# Steering_Converter_DRV8833C.net
KiCad netlist of a schematic drawn in Altium Designer
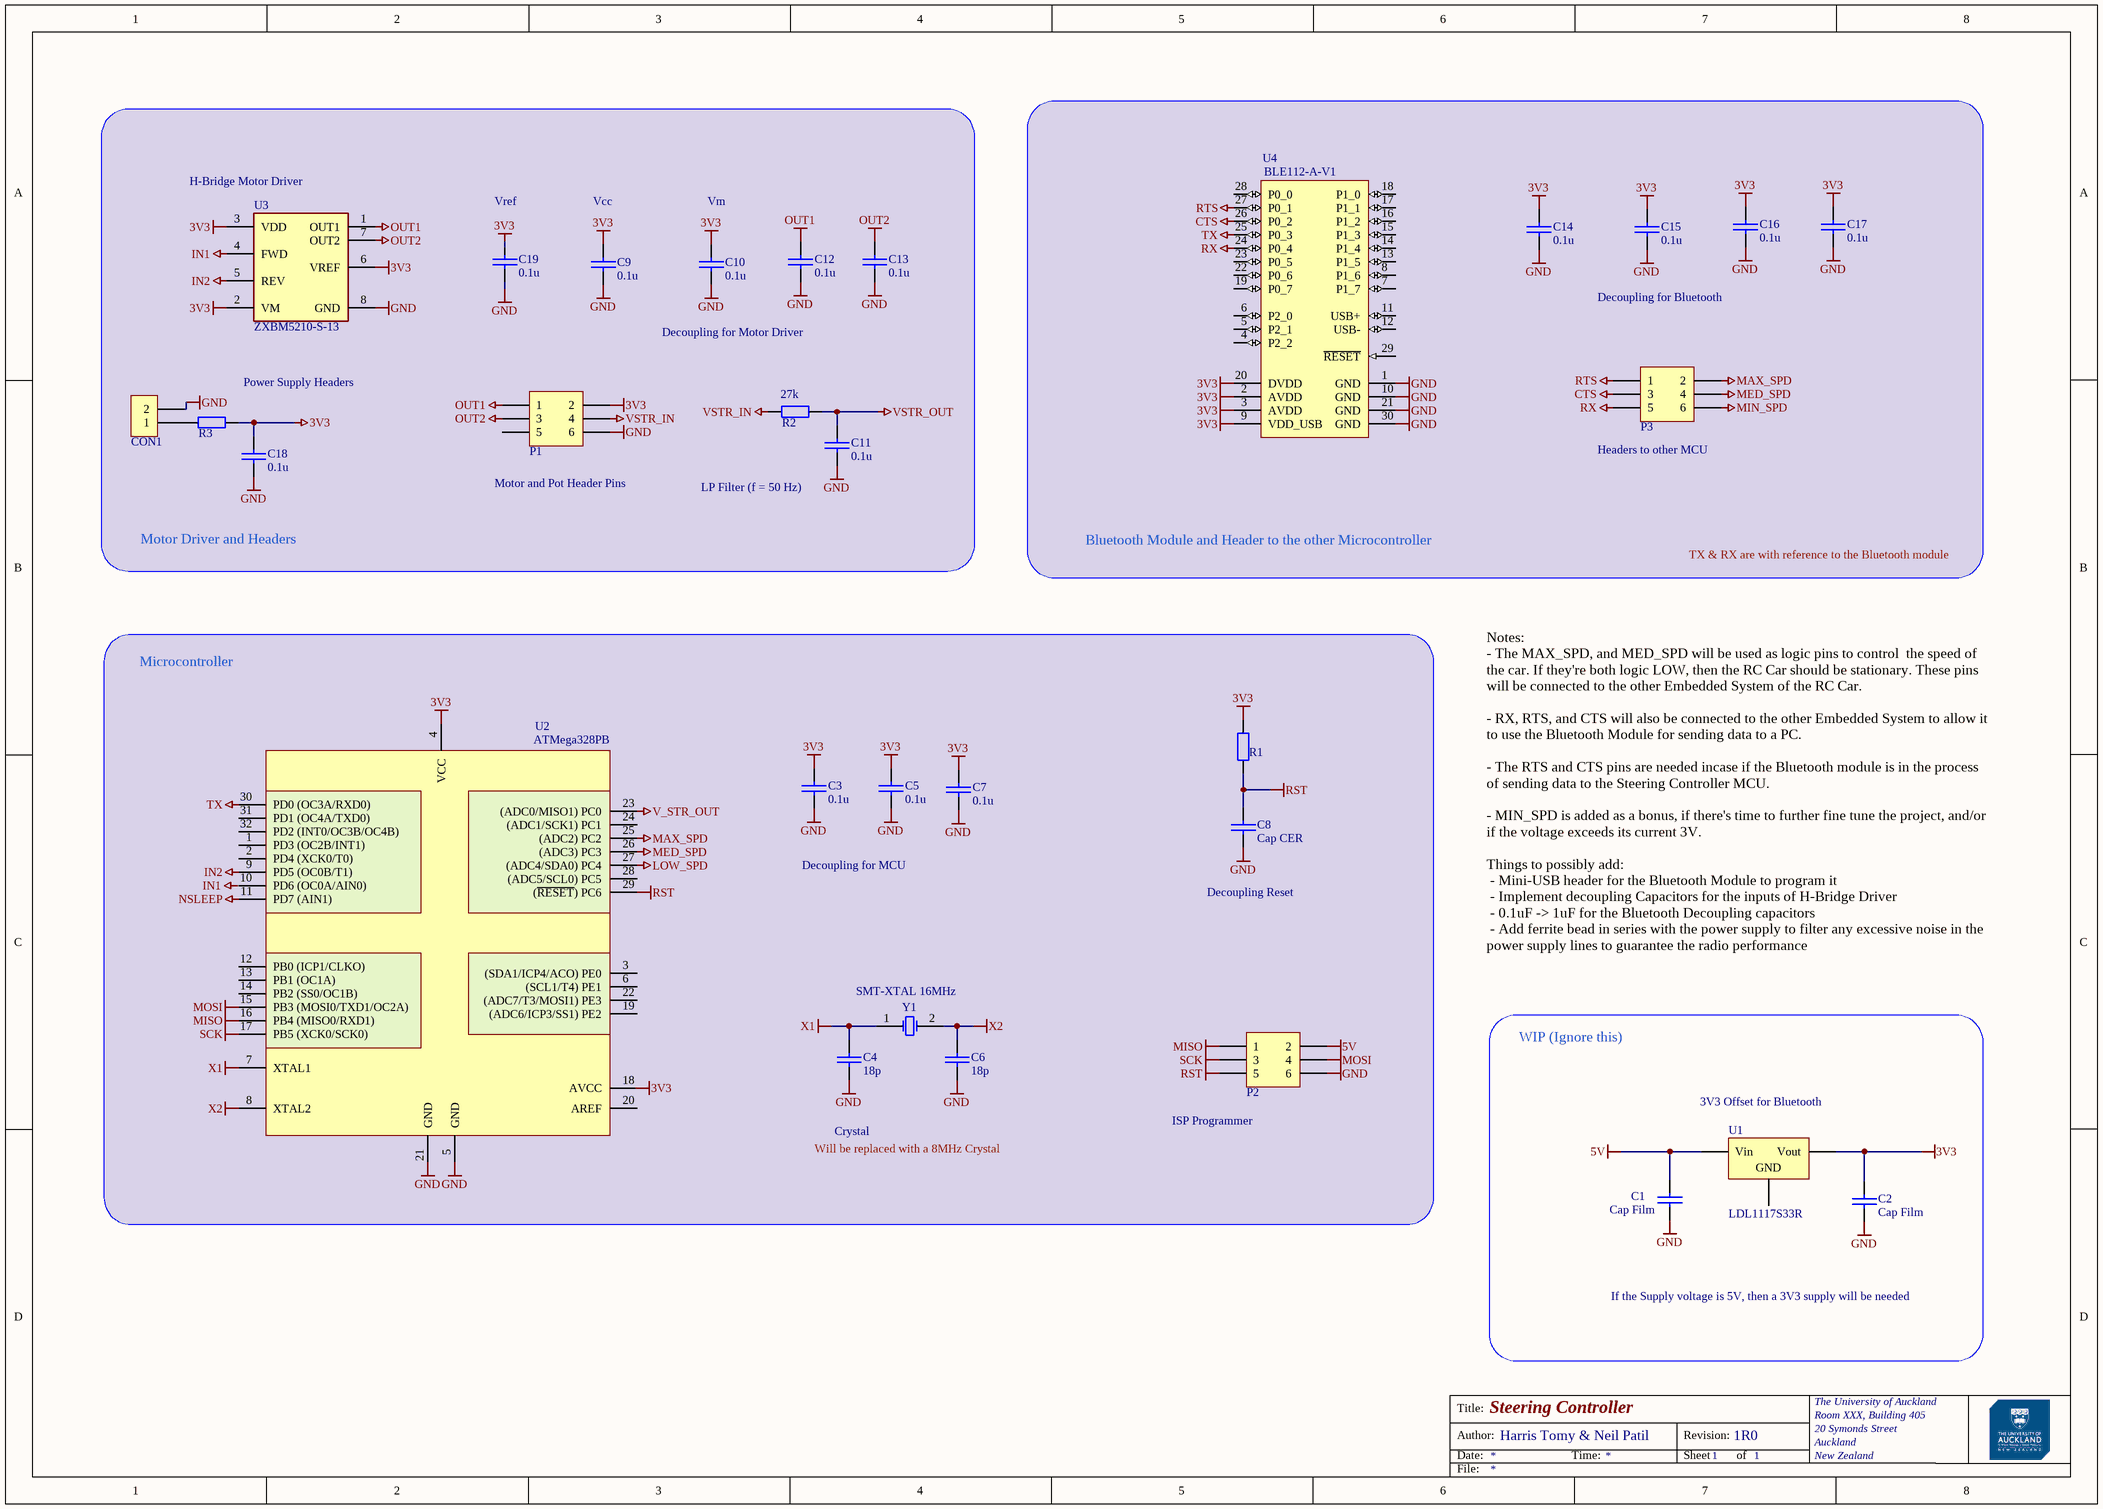
[diagram p0: Steering_Converter_DRV8833C.SchDoc]

(export (version "E")
  (design (tool "Eeschema 10.0.6"))
  (components
    (comp (ref "C1")
      (value "Cap Film")
      (footprint "LDECE4150KA0N00")
      (description "CAP FILM 1.5UF 10% 50VDC 2824")
      (fields (field (name "MPN") "LDECE4150KA0N00") (field (name "MANUFACTURER") "KEMET"))
      (libsource (lib "E209_Lib") (part "Cap Film SMD LDECE4150KA0N00"))
    )
    (comp (ref "C2")
      (value "Cap Film")
      (footprint "LDECE4150KA0N00")
      (description "CAP FILM 1.5UF 10% 50VDC 2824")
      (fields (field (name "MPN") "LDECE4150KA0N00") (field (name "MANUFACTURER") "KEMET"))
      (libsource (lib "E209_Lib") (part "Cap Film SMD LDECE4150KA0N00"))
    )
    (comp (ref "C3")
      (value "0.1u")
      (footprint "C1206")
      (description "CAP CER 0.1UF 100V C0G 1206")
      (fields (field (name "MPN") "C3216C0G2A104J160AC") (field (name "MANUFACTURER") "TDK Corporation"))
      (libsource (lib "E209_Lib") (part "Cap CER Decoup C3216C0G2A104J160AC"))
    )
    (comp (ref "C4")
      (value "18p")
      (footprint "C1206")
      (description "CAP CER 0.1UF 100V C0G 1206")
      (fields (field (name "MPN") "C3216C0G2A104J160AC") (field (name "MANUFACTURER") "TDK Corporation"))
      (libsource (lib "E209_Lib") (part "Cap CER Decoup C3216C0G2A104J160AC"))
    )
    (comp (ref "C5")
      (value "0.1u")
      (footprint "C1206")
      (description "CAP CER 0.1UF 100V C0G 1206")
      (fields (field (name "MPN") "C3216C0G2A104J160AC") (field (name "MANUFACTURER") "TDK Corporation"))
      (libsource (lib "E209_Lib") (part "Cap CER Decoup C3216C0G2A104J160AC"))
    )
    (comp (ref "C6")
      (value "18p")
      (footprint "C1206")
      (description "CAP CER 0.1UF 100V C0G 1206")
      (fields (field (name "MPN") "C3216C0G2A104J160AC") (field (name "MANUFACTURER") "TDK Corporation"))
      (libsource (lib "E209_Lib") (part "Cap CER Decoup C3216C0G2A104J160AC"))
    )
    (comp (ref "C7")
      (value "0.1u")
      (footprint "C1206")
      (description "CAP CER 0.1UF 100V C0G 1206")
      (fields (field (name "MPN") "C3216C0G2A104J160AC") (field (name "MANUFACTURER") "TDK Corporation"))
      (libsource (lib "E209_Lib") (part "Cap CER Decoup C3216C0G2A104J160AC"))
    )
    (comp (ref "C8")
      (value "Cap CER")
      (footprint "C1206")
      (description "CAP CER 0.1UF 100V C0G 1206")
      (fields (field (name "MPN") "C3216C0G2A104J160AC") (field (name "MANUFACTURER") "TDK Corporation"))
      (libsource (lib "E209_Lib") (part "Cap CER Decoup C3216C0G2A104J160AC"))
    )
    (comp (ref "C9")
      (value "0.1u")
      (footprint "C1206")
      (description "CAP CER 0.1UF 100V C0G 1206")
      (fields (field (name "MPN") "C3216C0G2A104J160AC") (field (name "MANUFACTURER") "TDK Corporation"))
      (libsource (lib "E209_Lib") (part "Cap CER Decoup C3216C0G2A104J160AC"))
    )
    (comp (ref "C10")
      (value "0.1u")
      (footprint "C1206")
      (description "CAP CER 0.1UF 100V C0G 1206")
      (fields (field (name "MPN") "C3216C0G2A104J160AC") (field (name "MANUFACTURER") "TDK Corporation"))
      (libsource (lib "E209_Lib") (part "Cap CER Decoup C3216C0G2A104J160AC"))
    )
    (comp (ref "C11")
      (value "0.1u")
      (footprint "C1206")
      (description "CAP CER 0.1UF 100V C0G 1206")
      (fields (field (name "MPN") "C3216C0G2A104J160AC") (field (name "MANUFACTURER") "TDK Corporation"))
      (libsource (lib "E209_Lib") (part "Cap CER Decoup C3216C0G2A104J160AC"))
    )
    (comp (ref "C12")
      (value "0.1u")
      (footprint "C1206")
      (description "CAP CER 0.1UF 100V C0G 1206")
      (fields (field (name "MPN") "C3216C0G2A104J160AC") (field (name "MANUFACTURER") "TDK Corporation"))
      (libsource (lib "E209_Lib") (part "Cap CER Decoup C3216C0G2A104J160AC"))
    )
    (comp (ref "C13")
      (value "0.1u")
      (footprint "C1206")
      (description "CAP CER 0.1UF 100V C0G 1206")
      (fields (field (name "MPN") "C3216C0G2A104J160AC") (field (name "MANUFACTURER") "TDK Corporation"))
      (libsource (lib "E209_Lib") (part "Cap CER Decoup C3216C0G2A104J160AC"))
    )
    (comp (ref "C14")
      (value "0.1u")
      (footprint "C1206")
      (description "CAP CER 0.1UF 100V C0G 1206")
      (fields (field (name "MPN") "C3216C0G2A104J160AC") (field (name "MANUFACTURER") "TDK Corporation"))
      (libsource (lib "E209_Lib") (part "Cap CER Decoup C3216C0G2A104J160AC"))
    )
    (comp (ref "C15")
      (value "0.1u")
      (footprint "C1206")
      (description "CAP CER 0.1UF 100V C0G 1206")
      (fields (field (name "MPN") "C3216C0G2A104J160AC") (field (name "MANUFACTURER") "TDK Corporation"))
      (libsource (lib "E209_Lib") (part "Cap CER Decoup C3216C0G2A104J160AC"))
    )
    (comp (ref "C16")
      (value "0.1u")
      (footprint "C1206")
      (description "CAP CER 0.1UF 100V C0G 1206")
      (fields (field (name "MPN") "C3216C0G2A104J160AC") (field (name "MANUFACTURER") "TDK Corporation"))
      (libsource (lib "E209_Lib") (part "Cap CER Decoup C3216C0G2A104J160AC"))
    )
    (comp (ref "C17")
      (value "0.1u")
      (footprint "C1206")
      (description "CAP CER 0.1UF 100V C0G 1206")
      (fields (field (name "MPN") "C3216C0G2A104J160AC") (field (name "MANUFACTURER") "TDK Corporation"))
      (libsource (lib "E209_Lib") (part "Cap CER Decoup C3216C0G2A104J160AC"))
    )
    (comp (ref "C18")
      (value "0.1u")
      (footprint "C1206")
      (description "CAP CER 0.1UF 100V C0G 1206")
      (fields (field (name "MPN") "C3216C0G2A104J160AC") (field (name "MANUFACTURER") "TDK Corporation"))
      (libsource (lib "E209_Lib") (part "Cap CER Decoup C3216C0G2A104J160AC"))
    )
    (comp (ref "C19")
      (value "0.1u")
      (footprint "C1206")
      (description "CAP CER 0.1UF 100V C0G 1206")
      (fields (field (name "MPN") "C3216C0G2A104J160AC") (field (name "MANUFACTURER") "TDK Corporation"))
      (libsource (lib "E209_Lib") (part "Cap CER Decoup C3216C0G2A104J160AC"))
    )
    (comp (ref "CON1")
      (value "Header 2X1")
      (footprint "HDR2X1_2P54")
      (libsource (lib "CommonDevices_V1") (part "HDR2X1"))
    )
    (comp (ref "P1")
      (value "HDR3X2")
      (footprint "HDR2X3_2P54")
      (description "Header, 3-Pin, Dual row")
      (libsource (lib "CommonDevices_V1") (part "HDR3X2"))
    )
    (comp (ref "P2")
      (value "HDR3X2")
      (footprint "HDR2X3_2P54")
      (description "Header, 3-Pin, Dual row")
      (libsource (lib "CommonDevices_V1") (part "HDR3X2"))
    )
    (comp (ref "P3")
      (value "HDR3X2")
      (footprint "HDR2X3_2P54")
      (description "Header, 3-Pin, Dual row")
      (libsource (lib "CommonDevices_V1") (part "HDR3X2"))
    )
    (comp (ref "R1")
      (value "Resistor 1206")
      (footprint "R1206")
      (description "RES1206")
      (fields (field (name "MPN") "?"))
      (libsource (lib "E209_Lib") (part "RES1206"))
    )
    (comp (ref "R2")
      (value "Resistor 0805")
      (footprint "R0805")
      (description "RES0805")
      (fields (field (name "MPN") "?"))
      (libsource (lib "E209_Lib") (part "RES0805"))
    )
    (comp (ref "R3")
      (value "Resistor 0805")
      (footprint "R0805")
      (description "RES0805")
      (fields (field (name "MPN") "?"))
      (libsource (lib "E209_Lib") (part "RES0805"))
    )
    (comp (ref "U1")
      (value "LDL1117S33R")
      (footprint "SOT223L")
      (description "IC REG LINEAR 3.3V 1.2A SOT223")
      (fields (field (name "MANUFACTURER") "STMicroelectronics"))
      (libsource (lib "E209_Lib") (part "LDO LDL1117S33R"))
    )
    (comp (ref "U2")
      (value "ATMega328PB")
      (footprint "TQFP32")
      (description "IC MCU 8BIT 32KB FLASH 32TQFP")
      (libsource (lib "CommonDevices_V1") (part "ATMega328PB"))
    )
    (comp (ref "U3")
      (value "IC_Diodes_ZXBM5210-S-13_eec")
      (footprint "Diodes_ZXBM5210-S-13_0")
      (description "IC MOTOR DRIVER PWM 8SOIC")
      (fields
        (field (name "PART NUMBER") "ZXBM5210-S-13")
        (field (name "VOLTAGE") "18V")
        (field (name "MANUFACTURER") "Diodes")
      )
      (libsource (lib "ZXBM5210-S-13") (part "IC_Diodes_ZXBM5210-S-13_eec"))
    )
    (comp (ref "U4")
      (value "BLE112-A-V1")
      (footprint "BLUE-BLE112-A-V1_V")
      (libsource (lib "Integrated_Library1") (part "BLE112-A-V1"))
    )
    (comp (ref "Y1")
      (value "SMT-XTAL 16MHz")
      (footprint "HC49-US")
      (description "9C-16.000MAAJ-T crystal 16.0000MHZ 18PF SMD")
      (fields
        (field (name "MANUFACTURER") "TXC CORPORATION")
        (field (name "MANUFACTURER PART NUMBER") "9C-16.000MAAJ-T")
      )
      (libsource (lib "EE209_Library") (part "TXC9C-16_XTAL_SMT"))
    )
  )
  (nets
    (net (code "1") (name "3V3") (class "Default")
      (node (ref "C10") (pin "2") (pinfunction "2_2") (pintype "passive"))
      (node (ref "C14") (pin "2") (pinfunction "2_2") (pintype "passive"))
      (node (ref "C15") (pin "2") (pinfunction "2_2") (pintype "passive"))
      (node (ref "C16") (pin "2") (pinfunction "2_2") (pintype "passive"))
      (node (ref "C17") (pin "2") (pinfunction "2_2") (pintype "passive"))
      (node (ref "C18") (pin "2") (pinfunction "2_2") (pintype "passive"))
      (node (ref "C19") (pin "2") (pinfunction "2_2") (pintype "passive"))
      (node (ref "C2") (pin "2") (pinfunction "2_2") (pintype "passive"))
      (node (ref "C3") (pin "2") (pinfunction "2_2") (pintype "passive"))
      (node (ref "C5") (pin "2") (pinfunction "2_2") (pintype "passive"))
      (node (ref "C7") (pin "2") (pinfunction "2_2") (pintype "passive"))
      (node (ref "C9") (pin "2") (pinfunction "2_2") (pintype "passive"))
      (node (ref "P1") (pin "2") (pinfunction "2_2") (pintype "passive"))
      (node (ref "R1") (pin "1") (pinfunction "1_1") (pintype "passive"))
      (node (ref "R3") (pin "2") (pinfunction "2_2") (pintype "passive"))
      (node (ref "U1") (pin "2") (pinfunction "Vout_2") (pintype "passive"))
      (node (ref "U2") (pin "4") (pinfunction "VCC_4") (pintype "passive"))
      (node (ref "U3") (pin "2") (pinfunction "VM_2") (pintype "passive"))
      (node (ref "U3") (pin "3") (pinfunction "VDD_3") (pintype "passive"))
      (node (ref "U3") (pin "6") (pinfunction "VREF_6") (pintype "passive"))
      (node (ref "U4") (pin "2") (pinfunction "AVDD_2") (pintype "power_in"))
      (node (ref "U4") (pin "20") (pinfunction "DVDD_20") (pintype "power_in"))
      (node (ref "U4") (pin "3") (pinfunction "AVDD_3") (pintype "power_in"))
      (node (ref "U4") (pin "9") (pinfunction "VDD_USB_9") (pintype "power_in"))
    )
    (net (code "2") (name "5V") (class "Default")
      (node (ref "C1") (pin "2") (pinfunction "2_2") (pintype "passive"))
      (node (ref "P2") (pin "2") (pinfunction "2_2") (pintype "passive"))
      (node (ref "U1") (pin "3") (pinfunction "Vin_3") (pintype "passive"))
    )
    (net (code "3") (name "CTS") (class "Default")
      (node (ref "P3") (pin "3") (pinfunction "3_3") (pintype "passive"))
      (node (ref "U4") (pin "26") (pinfunction "P0_2_26") (pintype "bidirectional"))
    )
    (net (code "4") (name "GND") (class "Default")
      (node (ref "C1") (pin "1") (pinfunction "1_1") (pintype "passive"))
      (node (ref "C10") (pin "1") (pinfunction "1_1") (pintype "passive"))
      (node (ref "C11") (pin "1") (pinfunction "1_1") (pintype "passive"))
      (node (ref "C12") (pin "1") (pinfunction "1_1") (pintype "passive"))
      (node (ref "C13") (pin "1") (pinfunction "1_1") (pintype "passive"))
      (node (ref "C14") (pin "1") (pinfunction "1_1") (pintype "passive"))
      (node (ref "C15") (pin "1") (pinfunction "1_1") (pintype "passive"))
      (node (ref "C16") (pin "1") (pinfunction "1_1") (pintype "passive"))
      (node (ref "C17") (pin "1") (pinfunction "1_1") (pintype "passive"))
      (node (ref "C18") (pin "1") (pinfunction "1_1") (pintype "passive"))
      (node (ref "C19") (pin "1") (pinfunction "1_1") (pintype "passive"))
      (node (ref "C2") (pin "1") (pinfunction "1_1") (pintype "passive"))
      (node (ref "C3") (pin "1") (pinfunction "1_1") (pintype "passive"))
      (node (ref "C4") (pin "1") (pinfunction "1_1") (pintype "passive"))
      (node (ref "C5") (pin "1") (pinfunction "1_1") (pintype "passive"))
      (node (ref "C6") (pin "1") (pinfunction "1_1") (pintype "passive"))
      (node (ref "C7") (pin "1") (pinfunction "1_1") (pintype "passive"))
      (node (ref "C8") (pin "1") (pinfunction "1_1") (pintype "passive"))
      (node (ref "C9") (pin "1") (pinfunction "1_1") (pintype "passive"))
      (node (ref "CON1") (pin "2") (pinfunction "2_2") (pintype "passive"))
      (node (ref "P1") (pin "6") (pinfunction "6_6") (pintype "passive"))
      (node (ref "P2") (pin "6") (pinfunction "6_6") (pintype "passive"))
      (node (ref "U2") (pin "21") (pinfunction "GND_21") (pintype "passive"))
      (node (ref "U2") (pin "5") (pinfunction "GND_5") (pintype "passive"))
      (node (ref "U3") (pin "8") (pinfunction "GND_8") (pintype "passive"))
      (node (ref "U4") (pin "1") (pinfunction "GND_1") (pintype "power_in"))
      (node (ref "U4") (pin "10") (pinfunction "GND_10") (pintype "power_in"))
      (node (ref "U4") (pin "21") (pinfunction "GND_21") (pintype "power_in"))
      (node (ref "U4") (pin "30") (pinfunction "GND_30") (pintype "power_in"))
    )
    (net (code "5") (name "IN1") (class "Default")
      (node (ref "U3") (pin "4") (pinfunction "FWD_4") (pintype "passive"))
    )
    (net (code "6") (name "IN2") (class "Default")
      (node (ref "U2") (pin "9") (pinfunction "PD5_(OC0B/T1)_9") (pintype "passive"))
      (node (ref "U3") (pin "5") (pinfunction "REV_5") (pintype "passive"))
    )
    (net (code "7") (name "LOW_SPD") (class "Default")
      (node (ref "U2") (pin "27") (pinfunction "(ADC4/SDA0)_PC4_27") (pintype "passive"))
    )
    (net (code "8") (name "MAX_SPD") (class "Default")
      (node (ref "P3") (pin "2") (pinfunction "2_2") (pintype "passive"))
      (node (ref "U2") (pin "25") (pinfunction "(ADC2)_PC2_25") (pintype "passive"))
    )
    (net (code "9") (name "MED_SPD") (class "Default")
      (node (ref "P3") (pin "4") (pinfunction "4_4") (pintype "passive"))
      (node (ref "U2") (pin "26") (pinfunction "(ADC3)_PC3_26") (pintype "passive"))
    )
    (net (code "10") (name "MIN_SPD") (class "Default")
      (node (ref "P3") (pin "6") (pinfunction "6_6") (pintype "passive"))
    )
    (net (code "11") (name "MISO") (class "Default")
      (node (ref "P2") (pin "1") (pinfunction "1_1") (pintype "passive"))
      (node (ref "U2") (pin "16") (pinfunction "PB4_(MISO0/RXD1)_16") (pintype "passive"))
    )
    (net (code "12") (name "MOSI") (class "Default")
      (node (ref "P2") (pin "4") (pinfunction "4_4") (pintype "passive"))
      (node (ref "U2") (pin "15") (pinfunction "PB3_(MOSI0/TXD1/OC2A)_15") (pintype "passive"))
    )
    (net (code "13") (name "NSLEEP") (class "Default")
      (node (ref "U2") (pin "11") (pinfunction "PD7_(AIN1)_11") (pintype "passive"))
    )
    (net (code "14") (name "Net-(CON1-Pad1)") (class "Default")
      (node (ref "CON1") (pin "1") (pinfunction "1_1") (pintype "passive"))
      (node (ref "R3") (pin "1") (pinfunction "1_1") (pintype "passive"))
    )
    (net (code "15") (name "OUT1") (class "Default")
      (node (ref "C12") (pin "2") (pinfunction "2_2") (pintype "passive"))
      (node (ref "P1") (pin "1") (pinfunction "1_1") (pintype "passive"))
      (node (ref "U3") (pin "1") (pinfunction "OUT1_1") (pintype "passive"))
    )
    (net (code "16") (name "OUT2") (class "Default")
      (node (ref "C13") (pin "2") (pinfunction "2_2") (pintype "passive"))
      (node (ref "P1") (pin "3") (pinfunction "3_3") (pintype "passive"))
      (node (ref "U3") (pin "7") (pinfunction "OUT2_7") (pintype "passive"))
    )
    (net (code "17") (name "RST") (class "Default")
      (node (ref "C8") (pin "2") (pinfunction "2_2") (pintype "passive"))
      (node (ref "P2") (pin "5") (pinfunction "5_5") (pintype "passive"))
      (node (ref "R1") (pin "2") (pinfunction "2_2") (pintype "passive"))
      (node (ref "U2") (pin "29") (pinfunction "(~{RESET})_PC6_29") (pintype "passive"))
    )
    (net (code "18") (name "RTS") (class "Default")
      (node (ref "P3") (pin "1") (pinfunction "1_1") (pintype "passive"))
      (node (ref "U4") (pin "27") (pinfunction "P0_1_27") (pintype "bidirectional"))
    )
    (net (code "19") (name "RX") (class "Default")
      (node (ref "P3") (pin "5") (pinfunction "5_5") (pintype "passive"))
      (node (ref "U4") (pin "24") (pinfunction "P0_4_24") (pintype "bidirectional"))
    )
    (net (code "20") (name "SCK") (class "Default")
      (node (ref "P2") (pin "3") (pinfunction "3_3") (pintype "passive"))
      (node (ref "U2") (pin "17") (pinfunction "PB5_(XCK0/SCK0)_17") (pintype "passive"))
    )
    (net (code "21") (name "TX") (class "Default")
      (node (ref "U2") (pin "30") (pinfunction "PD0_(OC3A/RXD0)_30") (pintype "passive"))
      (node (ref "U4") (pin "25") (pinfunction "P0_3_25") (pintype "bidirectional"))
    )
    (net (code "22") (name "VSTR_IN") (class "Default")
      (node (ref "P1") (pin "4") (pinfunction "4_4") (pintype "passive"))
      (node (ref "R2") (pin "1") (pinfunction "1_1") (pintype "passive"))
    )
    (net (code "23") (name "VSTR_OUT") (class "Default")
      (node (ref "C11") (pin "2") (pinfunction "2_2") (pintype "passive"))
      (node (ref "R2") (pin "2") (pinfunction "2_2") (pintype "passive"))
    )
    (net (code "24") (name "V_STR_OUT") (class "Default")
      (node (ref "U2") (pin "23") (pinfunction "(ADC0/MISO1)_PC0_23") (pintype "passive"))
    )
    (net (code "25") (name "X1") (class "Default")
      (node (ref "C4") (pin "2") (pinfunction "2_2") (pintype "passive"))
      (node (ref "U2") (pin "7") (pinfunction "XTAL1_7") (pintype "passive"))
      (node (ref "Y1") (pin "1") (pinfunction "OSC1_1") (pintype "passive"))
    )
    (net (code "26") (name "X2") (class "Default")
      (node (ref "C6") (pin "2") (pinfunction "2_2") (pintype "passive"))
      (node (ref "U2") (pin "8") (pinfunction "XTAL2_8") (pintype "passive"))
      (node (ref "Y1") (pin "2") (pinfunction "OSC2_2") (pintype "passive"))
    )
    (net (code "27") (name "unconnected-(P1-Pad5)") (class "Default")
      (node (ref "P1") (pin "5") (pinfunction "5_5") (pintype "passive"))
    )
    (net (code "28") (name "unconnected-(U1-GND-Pad1)") (class "Default")
      (node (ref "U1") (pin "1") (pinfunction "GND_1") (pintype "passive"))
    )
    (net (code "29") (name "unconnected-(U2-(ADC1{slash}SCK1)_PC1-Pad24)") (class "Default")
      (node (ref "U2") (pin "24") (pinfunction "(ADC1/SCK1)_PC1_24") (pintype "passive"))
    )
    (net (code "30") (name "unconnected-(U2-(ADC5{slash}SCL0)_PC5-Pad28)") (class "Default")
      (node (ref "U2") (pin "28") (pinfunction "(ADC5/SCL0)_PC5_28") (pintype "passive"))
    )
    (net (code "31") (name "unconnected-(U2-(ADC6{slash}ICP3{slash}SS1)_PE2-Pad19)") (class "Default")
      (node (ref "U2") (pin "19") (pinfunction "(ADC6/ICP3/SS1)_PE2_19") (pintype "passive"))
    )
    (net (code "32") (name "unconnected-(U2-(ADC7{slash}T3{slash}MOSI1)_PE3-Pad22)") (class "Default")
      (node (ref "U2") (pin "22") (pinfunction "(ADC7/T3/MOSI1)_PE3_22") (pintype "passive"))
    )
    (net (code "33") (name "unconnected-(U2-(SCL1{slash}T4)_PE1-Pad6)") (class "Default")
      (node (ref "U2") (pin "6") (pinfunction "(SCL1/T4)_PE1_6") (pintype "passive"))
    )
    (net (code "34") (name "unconnected-(U2-(SDA1{slash}ICP4{slash}ACO)_PE0-Pad3)") (class "Default")
      (node (ref "U2") (pin "3") (pinfunction "(SDA1/ICP4/ACO)_PE0_3") (pintype "passive"))
    )
    (net (code "35") (name "unconnected-(U2-AREF-Pad20)") (class "Default")
      (node (ref "U2") (pin "20") (pinfunction "AREF_20") (pintype "passive"))
    )
    (net (code "36") (name "unconnected-(U2-AVCC-Pad18)") (class "Default")
      (node (ref "U2") (pin "18") (pinfunction "AVCC_18") (pintype "passive"))
    )
    (net (code "37") (name "unconnected-(U2-PB0_(ICP1{slash}CLKO)-Pad12)") (class "Default")
      (node (ref "U2") (pin "12") (pinfunction "PB0_(ICP1/CLKO)_12") (pintype "passive"))
    )
    (net (code "38") (name "unconnected-(U2-PB1_(OC1A)-Pad13)") (class "Default")
      (node (ref "U2") (pin "13") (pinfunction "PB1_(OC1A)_13") (pintype "passive"))
    )
    (net (code "39") (name "unconnected-(U2-PB2_(SS0{slash}OC1B)-Pad14)") (class "Default")
      (node (ref "U2") (pin "14") (pinfunction "PB2_(SS0/OC1B)_14") (pintype "passive"))
    )
    (net (code "40") (name "unconnected-(U2-PD1_(OC4A{slash}TXD0)-Pad31)") (class "Default")
      (node (ref "U2") (pin "31") (pinfunction "PD1_(OC4A/TXD0)_31") (pintype "passive"))
    )
    (net (code "41") (name "unconnected-(U2-PD2_(INT0{slash}OC3B{slash}OC4B)-Pad32)") (class "Default")
      (node (ref "U2") (pin "32") (pinfunction "PD2_(INT0/OC3B/OC4B)_32") (pintype "passive"))
    )
    (net (code "42") (name "unconnected-(U2-PD3_(OC2B{slash}INT1)-Pad1)") (class "Default")
      (node (ref "U2") (pin "1") (pinfunction "PD3_(OC2B/INT1)_1") (pintype "passive"))
    )
    (net (code "43") (name "unconnected-(U2-PD4_(XCK0{slash}T0)-Pad2)") (class "Default")
      (node (ref "U2") (pin "2") (pinfunction "PD4_(XCK0/T0)_2") (pintype "passive"))
    )
    (net (code "44") (name "unconnected-(U2-PD6_(OC0A{slash}AIN0)-Pad10)") (class "Default")
      (node (ref "U2") (pin "10") (pinfunction "PD6_(OC0A/AIN0)_10") (pintype "passive"))
    )
    (net (code "45") (name "unconnected-(U4-P0_0-Pad28)") (class "Default")
      (node (ref "U4") (pin "28") (pinfunction "P0_0_28") (pintype "bidirectional"))
    )
    (net (code "46") (name "unconnected-(U4-P0_5-Pad23)") (class "Default")
      (node (ref "U4") (pin "23") (pinfunction "P0_5_23") (pintype "bidirectional"))
    )
    (net (code "47") (name "unconnected-(U4-P0_6-Pad22)") (class "Default")
      (node (ref "U4") (pin "22") (pinfunction "P0_6_22") (pintype "bidirectional"))
    )
    (net (code "48") (name "unconnected-(U4-P0_7-Pad19)") (class "Default")
      (node (ref "U4") (pin "19") (pinfunction "P0_7_19") (pintype "bidirectional"))
    )
    (net (code "49") (name "unconnected-(U4-P1_0-Pad18)") (class "Default")
      (node (ref "U4") (pin "18") (pinfunction "P1_0_18") (pintype "bidirectional"))
    )
    (net (code "50") (name "unconnected-(U4-P1_1-Pad17)") (class "Default")
      (node (ref "U4") (pin "17") (pinfunction "P1_1_17") (pintype "bidirectional"))
    )
    (net (code "51") (name "unconnected-(U4-P1_2-Pad16)") (class "Default")
      (node (ref "U4") (pin "16") (pinfunction "P1_2_16") (pintype "bidirectional"))
    )
    (net (code "52") (name "unconnected-(U4-P1_3-Pad15)") (class "Default")
      (node (ref "U4") (pin "15") (pinfunction "P1_3_15") (pintype "bidirectional"))
    )
    (net (code "53") (name "unconnected-(U4-P1_4-Pad14)") (class "Default")
      (node (ref "U4") (pin "14") (pinfunction "P1_4_14") (pintype "bidirectional"))
    )
    (net (code "54") (name "unconnected-(U4-P1_5-Pad13)") (class "Default")
      (node (ref "U4") (pin "13") (pinfunction "P1_5_13") (pintype "bidirectional"))
    )
    (net (code "55") (name "unconnected-(U4-P1_6-Pad8)") (class "Default")
      (node (ref "U4") (pin "8") (pinfunction "P1_6_8") (pintype "bidirectional"))
    )
    (net (code "56") (name "unconnected-(U4-P1_7-Pad7)") (class "Default")
      (node (ref "U4") (pin "7") (pinfunction "P1_7_7") (pintype "bidirectional"))
    )
    (net (code "57") (name "unconnected-(U4-P2_0-Pad6)") (class "Default")
      (node (ref "U4") (pin "6") (pinfunction "P2_0_6") (pintype "bidirectional"))
    )
    (net (code "58") (name "unconnected-(U4-P2_1-Pad5)") (class "Default")
      (node (ref "U4") (pin "5") (pinfunction "P2_1_5") (pintype "bidirectional"))
    )
    (net (code "59") (name "unconnected-(U4-P2_2-Pad4)") (class "Default")
      (node (ref "U4") (pin "4") (pinfunction "P2_2_4") (pintype "bidirectional"))
    )
    (net (code "60") (name "unconnected-(U4-USB+-Pad11)") (class "Default")
      (node (ref "U4") (pin "11") (pinfunction "USB+_11") (pintype "bidirectional"))
    )
    (net (code "61") (name "unconnected-(U4-USB--Pad12)") (class "Default")
      (node (ref "U4") (pin "12") (pinfunction "USB-_12") (pintype "bidirectional"))
    )
    (net (code "62") (name "unconnected-(U4-~{RESET}-Pad29)") (class "Default")
      (node (ref "U4") (pin "29") (pinfunction "~{RESET}_29") (pintype "input"))
    )
  )
)
